# Main.net
KiCad netlist of a schematic drawn in EAGLE
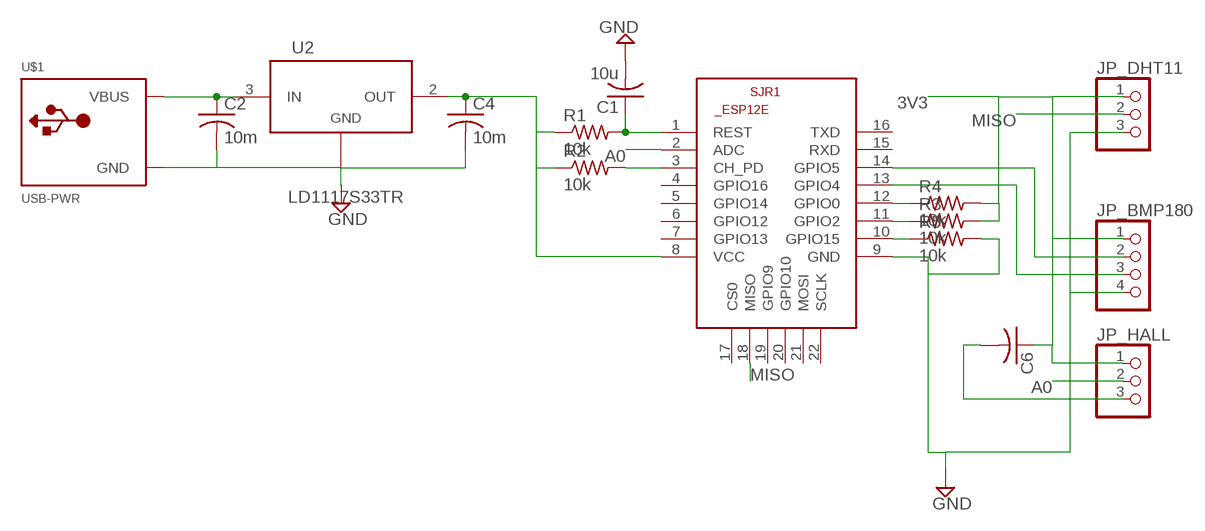
[diagram p0: schematic, sheet 1]

(export (version "E")
  (design (tool "Eeschema 10.0.6"))
  (components
    (comp (ref "C1")
      (value "10u")
      (footprint "eagle-import:C0805")
      (libsource (lib "eagle-import") (part "C-USC0805"))
    )
    (comp (ref "C2")
      (value "10m")
      (footprint "eagle-import:C0805")
      (libsource (lib "eagle-import") (part "C-USC0805"))
    )
    (comp (ref "C4")
      (value "10m")
      (footprint "eagle-import:C0805")
      (libsource (lib "eagle-import") (part "C-USC0805"))
    )
    (comp (ref "C6")
      (value "C-USC0805")
      (footprint "eagle-import:C0805")
      (libsource (lib "eagle-import") (part "C-USC0805"))
    )
    (comp (ref "JP_BMP180")
      (value "PINHD-1X4/90")
      (footprint "eagle-import:1X04_90")
      (libsource (lib "eagle-import") (part "PINHD-1X4/90"))
    )
    (comp (ref "JP_DHT11")
      (value "PINHD-1X3/90")
      (footprint "eagle-import:1X03_90")
      (libsource (lib "eagle-import") (part "PINHD-1X3/90"))
    )
    (comp (ref "JP_HALL")
      (value "PINHD-1X3/90")
      (footprint "eagle-import:1X03_90")
      (libsource (lib "eagle-import") (part "PINHD-1X3/90"))
    )
    (comp (ref "R1")
      (value "10k")
      (footprint "eagle-import:M1406")
      (libsource (lib "eagle-import") (part "R-US_M1406"))
    )
    (comp (ref "R2")
      (value "10k")
      (footprint "eagle-import:M1406")
      (libsource (lib "eagle-import") (part "R-US_M1406"))
    )
    (comp (ref "R3")
      (value "10k")
      (footprint "eagle-import:M1406")
      (libsource (lib "eagle-import") (part "R-US_M1406"))
    )
    (comp (ref "R4")
      (value "10k")
      (footprint "eagle-import:M1406")
      (libsource (lib "eagle-import") (part "R-US_M1406"))
    )
    (comp (ref "R5")
      (value "10k")
      (footprint "eagle-import:M1406")
      (libsource (lib "eagle-import") (part "R-US_M1406"))
    )
    (comp (ref "SJR1")
      (value "ESP8266-12EESP12E")
      (footprint "eagle-import:ESP8266-ESP12E")
      (libsource (lib "eagle-import") (part "ESP8266-12EESP12E"))
    )
    (comp (ref "U$1")
      (value "USB-PWR")
      (footprint "eagle-import:USB-MINIB-THM-MOLEX-PWRONLY")
      (libsource (lib "eagle-import") (part "USB-PWR"))
    )
    (comp (ref "U2")
      (value "LD1117S33TR")
      (footprint "eagle-import:SOT-223")
      (fields
        (field (name "DIGIKEY_PART_NUMBER") "497-1242-2-ND")
        (field (name "MANUFACTURER") "STMicroelectronics")
        (field (name "CREATED_BY") "PCBLayout.com")
      )
      (libsource (lib "eagle-import") (part "LD1117S33TR"))
    )
  )
  (nets
    (net (code "1") (name "/3V3") (class "Default")
      (node (ref "C4") (pin "1") (pinfunction "1_1") (pintype "passive"))
      (node (ref "C6") (pin "1") (pinfunction "1_1") (pintype "passive"))
      (node (ref "JP_BMP180") (pin "1") (pinfunction "1_1") (pintype "passive"))
      (node (ref "JP_DHT11") (pin "1") (pinfunction "1_1") (pintype "passive"))
      (node (ref "JP_HALL") (pin "1") (pinfunction "1_1") (pintype "passive"))
      (node (ref "R1") (pin "1") (pinfunction "1_1") (pintype "passive"))
      (node (ref "R2") (pin "1") (pinfunction "1_1") (pintype "passive"))
      (node (ref "R3") (pin "2") (pinfunction "2_2") (pintype "passive"))
      (node (ref "R4") (pin "2") (pinfunction "2_2") (pintype "passive"))
      (node (ref "SJR1") (pin "8") (pinfunction "VCC_8") (pintype "bidirectional"))
      (node (ref "U2") (pin "2") (pinfunction "OUT_2") (pintype "output"))
      (node (ref "U2") (pin "4") (pinfunction "4_4") (pintype "passive"))
    )
    (net (code "2") (name "/A0") (class "Default")
      (node (ref "JP_HALL") (pin "2") (pinfunction "2_2") (pintype "passive"))
      (node (ref "SJR1") (pin "2") (pinfunction "ADC_2") (pintype "bidirectional"))
    )
    (net (code "3") (name "/MISO") (class "Default")
      (node (ref "JP_DHT11") (pin "2") (pinfunction "2_2") (pintype "passive"))
      (node (ref "SJR1") (pin "18") (pinfunction "MISO_18") (pintype "bidirectional"))
    )
    (net (code "4") (name "GND") (class "Default")
      (node (ref "C1") (pin "2") (pinfunction "2_2") (pintype "passive"))
      (node (ref "C2") (pin "2") (pinfunction "2_2") (pintype "passive"))
      (node (ref "C4") (pin "2") (pinfunction "2_2") (pintype "passive"))
      (node (ref "C6") (pin "2") (pinfunction "2_2") (pintype "passive"))
      (node (ref "JP_BMP180") (pin "4") (pinfunction "4_4") (pintype "passive"))
      (node (ref "JP_DHT11") (pin "3") (pinfunction "3_3") (pintype "passive"))
      (node (ref "JP_HALL") (pin "3") (pinfunction "3_3") (pintype "passive"))
      (node (ref "R5") (pin "2") (pinfunction "2_2") (pintype "passive"))
      (node (ref "SJR1") (pin "9") (pinfunction "GND_9") (pintype "bidirectional"))
      (node (ref "U$1") (pin "GND") (pinfunction "GND_GND") (pintype "power_in"))
      (node (ref "U2") (pin "1") (pinfunction "ADJ/GND_1") (pintype "power_in"))
    )
    (net (code "5") (name "Net-(SJR1-CH_PD)") (class "Default")
      (node (ref "R2") (pin "2") (pinfunction "2_2") (pintype "passive"))
      (node (ref "SJR1") (pin "3") (pinfunction "CH_PD_3") (pintype "bidirectional"))
    )
    (net (code "6") (name "Net-(SJR1-GPIO0)") (class "Default")
      (node (ref "R4") (pin "1") (pinfunction "1_1") (pintype "passive"))
      (node (ref "SJR1") (pin "12") (pinfunction "GPIO0_12") (pintype "bidirectional"))
    )
    (net (code "7") (name "Net-(SJR1-GPIO2)") (class "Default")
      (node (ref "R3") (pin "1") (pinfunction "1_1") (pintype "passive"))
      (node (ref "SJR1") (pin "11") (pinfunction "GPIO2_11") (pintype "bidirectional"))
    )
    (net (code "8") (name "Net-(SJR1-GPIO4)") (class "Default")
      (node (ref "JP_BMP180") (pin "3") (pinfunction "3_3") (pintype "passive"))
      (node (ref "SJR1") (pin "13") (pinfunction "GPIO4_13") (pintype "bidirectional"))
    )
    (net (code "9") (name "Net-(SJR1-GPIO5)") (class "Default")
      (node (ref "JP_BMP180") (pin "2") (pinfunction "2_2") (pintype "passive"))
      (node (ref "SJR1") (pin "14") (pinfunction "GPIO5_14") (pintype "bidirectional"))
    )
    (net (code "10") (name "Net-(SJR1-GPIO15)") (class "Default")
      (node (ref "R5") (pin "1") (pinfunction "1_1") (pintype "passive"))
      (node (ref "SJR1") (pin "10") (pinfunction "GPIO15_10") (pintype "bidirectional"))
    )
    (net (code "11") (name "Net-(SJR1-REST)") (class "Default")
      (node (ref "C1") (pin "1") (pinfunction "1_1") (pintype "passive"))
      (node (ref "R1") (pin "2") (pinfunction "2_2") (pintype "passive"))
      (node (ref "SJR1") (pin "1") (pinfunction "REST_1") (pintype "bidirectional"))
    )
    (net (code "12") (name "Net-(U2-IN)") (class "Default")
      (node (ref "C2") (pin "1") (pinfunction "1_1") (pintype "passive"))
      (node (ref "U$1") (pin "VBUS") (pinfunction "VBUS_VBUS") (pintype "power_in"))
      (node (ref "U2") (pin "3") (pinfunction "IN_3") (pintype "input"))
    )
    (net (code "13") (name "unconnected-(SJR1-CS0-Pad17)") (class "Default")
      (node (ref "SJR1") (pin "17") (pinfunction "CS0_17") (pintype "bidirectional"))
    )
    (net (code "14") (name "unconnected-(SJR1-GPIO9-Pad19)") (class "Default")
      (node (ref "SJR1") (pin "19") (pinfunction "GPIO9_19") (pintype "bidirectional"))
    )
    (net (code "15") (name "unconnected-(SJR1-GPIO10-Pad20)") (class "Default")
      (node (ref "SJR1") (pin "20") (pinfunction "GPIO10_20") (pintype "bidirectional"))
    )
    (net (code "16") (name "unconnected-(SJR1-GPIO12-Pad6)") (class "Default")
      (node (ref "SJR1") (pin "6") (pinfunction "GPIO12_6") (pintype "bidirectional"))
    )
    (net (code "17") (name "unconnected-(SJR1-GPIO13-Pad7)") (class "Default")
      (node (ref "SJR1") (pin "7") (pinfunction "GPIO13_7") (pintype "bidirectional"))
    )
    (net (code "18") (name "unconnected-(SJR1-GPIO14-Pad5)") (class "Default")
      (node (ref "SJR1") (pin "5") (pinfunction "GPIO14_5") (pintype "bidirectional"))
    )
    (net (code "19") (name "unconnected-(SJR1-GPIO16-Pad4)") (class "Default")
      (node (ref "SJR1") (pin "4") (pinfunction "GPIO16_4") (pintype "bidirectional"))
    )
    (net (code "20") (name "unconnected-(SJR1-MOSI-Pad21)") (class "Default")
      (node (ref "SJR1") (pin "21") (pinfunction "MOSI_21") (pintype "bidirectional"))
    )
    (net (code "21") (name "unconnected-(SJR1-RXD-Pad15)") (class "Default")
      (node (ref "SJR1") (pin "15") (pinfunction "RXD_15") (pintype "bidirectional"))
    )
    (net (code "22") (name "unconnected-(SJR1-SCLK-Pad22)") (class "Default")
      (node (ref "SJR1") (pin "22") (pinfunction "SCLK_22") (pintype "bidirectional"))
    )
    (net (code "23") (name "unconnected-(SJR1-TXD-Pad16)") (class "Default")
      (node (ref "SJR1") (pin "16") (pinfunction "TXD_16") (pintype "bidirectional"))
    )
  )
)
